# design.net
KiCad netlist of a schematic drawn in Altium Designer
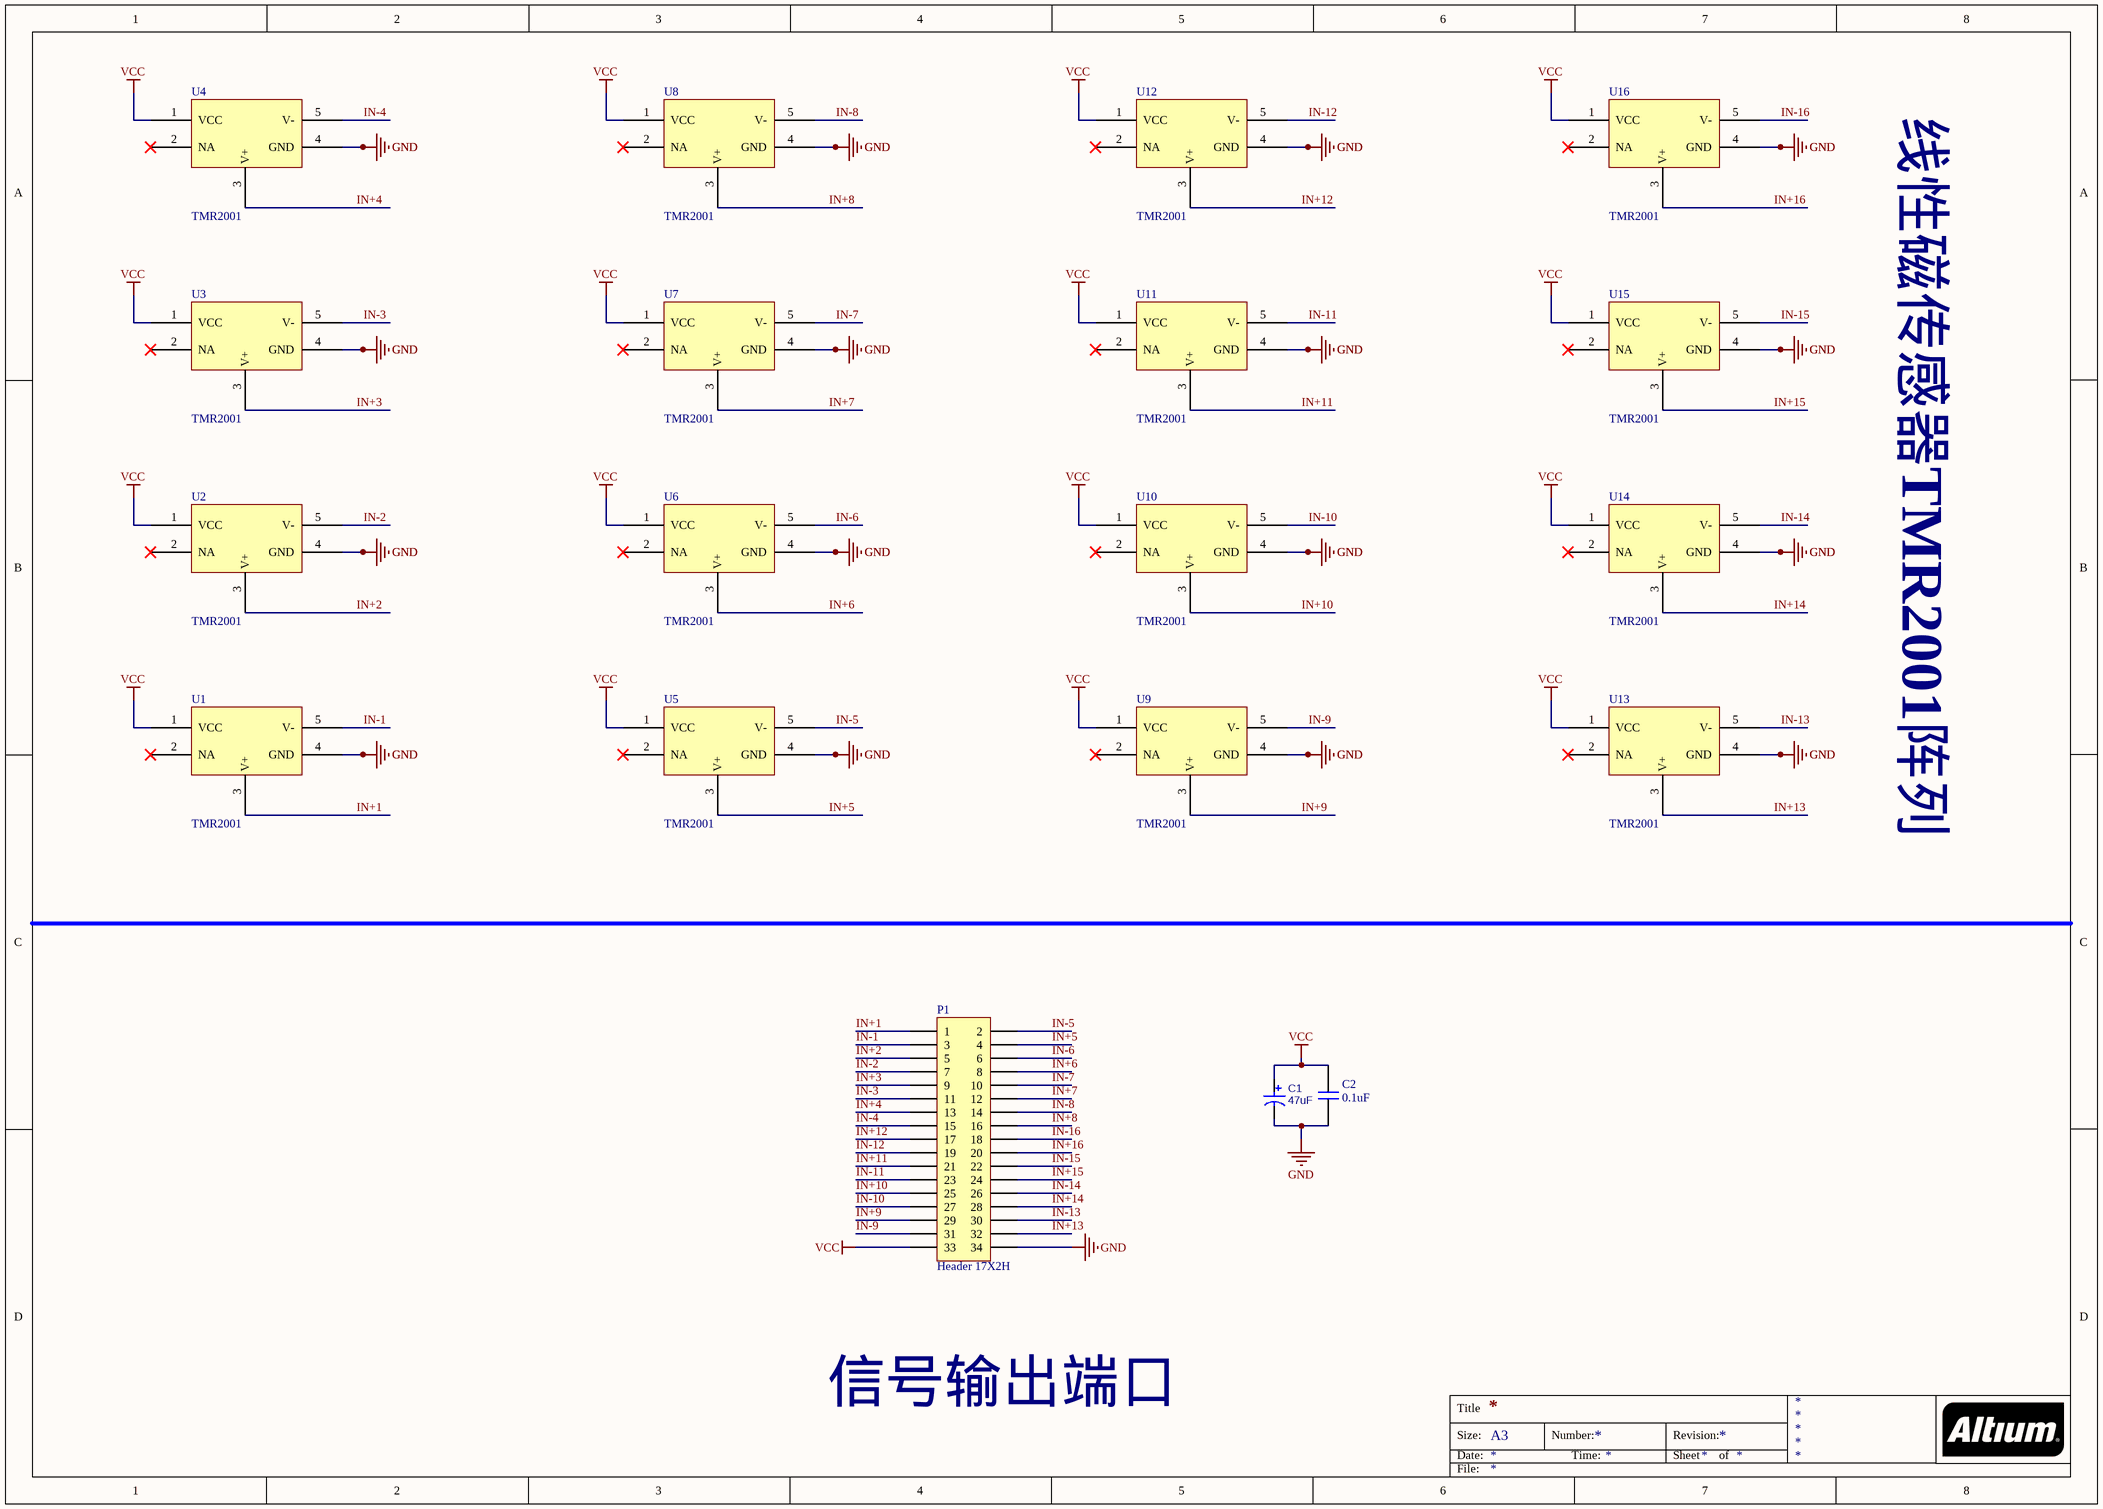
[diagram p0: 阵列磁传感器.SchDoc]

(export (version "E")
  (design (tool "Eeschema 10.0.6"))
  (components
    (comp (ref "C1")
      (value "47uF")
      (footprint "CAP-SMD_BD6.3-L6.6-W6.6-LS7.2-FD")
      (description "极性电解电容")
      (fields
        (field (name "BOM_MANUFACTURER PART") "Non - polar electrolytic capacitors10uf 100v")
        (field (name "BOM_SUPPLIER PART") "C56706")
      )
      (libsource (lib "毕业设计") (part "10uF"))
    )
    (comp (ref "C2")
      (value "0.1uF")
      (footprint "0805C")
      (description "普通电容")
      (libsource (lib "毕业设计") (part "CAP"))
    )
    (comp (ref "P1")
      (value "Header 17X2H")
      (footprint "HDR2X17")
      (description "Header, 17-Pin, Dual row, Right Angle")
      (fields (field (name "PUBLISHER") "Altium Limited"))
      (libsource (lib "Miscellaneous Connectors") (part "Header 17X2H"))
    )
    (comp (ref "U1")
      (value "TMR2001")
      (footprint "SOT95P280X145-5N")
      (description "线性磁传感器")
      (libsource (lib "毕业设计") (part "TMR2001"))
    )
    (comp (ref "U2")
      (value "TMR2001")
      (footprint "SOT95P280X145-5N")
      (description "线性磁传感器")
      (libsource (lib "毕业设计") (part "TMR2001"))
    )
    (comp (ref "U3")
      (value "TMR2001")
      (footprint "SOT95P280X145-5N")
      (description "线性磁传感器")
      (libsource (lib "毕业设计") (part "TMR2001"))
    )
    (comp (ref "U4")
      (value "TMR2001")
      (footprint "SOT95P280X145-5N")
      (description "线性磁传感器")
      (libsource (lib "毕业设计") (part "TMR2001"))
    )
    (comp (ref "U5")
      (value "TMR2001")
      (footprint "SOT95P280X145-5N")
      (description "线性磁传感器")
      (libsource (lib "毕业设计") (part "TMR2001"))
    )
    (comp (ref "U6")
      (value "TMR2001")
      (footprint "SOT95P280X145-5N")
      (description "线性磁传感器")
      (libsource (lib "毕业设计") (part "TMR2001"))
    )
    (comp (ref "U7")
      (value "TMR2001")
      (footprint "SOT95P280X145-5N")
      (description "线性磁传感器")
      (libsource (lib "毕业设计") (part "TMR2001"))
    )
    (comp (ref "U8")
      (value "TMR2001")
      (footprint "SOT95P280X145-5N")
      (description "线性磁传感器")
      (libsource (lib "毕业设计") (part "TMR2001"))
    )
    (comp (ref "U9")
      (value "TMR2001")
      (footprint "SOT95P280X145-5N")
      (description "线性磁传感器")
      (libsource (lib "毕业设计") (part "TMR2001"))
    )
    (comp (ref "U10")
      (value "TMR2001")
      (footprint "SOT95P280X145-5N")
      (description "线性磁传感器")
      (libsource (lib "毕业设计") (part "TMR2001"))
    )
    (comp (ref "U11")
      (value "TMR2001")
      (footprint "SOT95P280X145-5N")
      (description "线性磁传感器")
      (libsource (lib "毕业设计") (part "TMR2001"))
    )
    (comp (ref "U12")
      (value "TMR2001")
      (footprint "SOT95P280X145-5N")
      (description "线性磁传感器")
      (libsource (lib "毕业设计") (part "TMR2001"))
    )
    (comp (ref "U13")
      (value "TMR2001")
      (footprint "SOT95P280X145-5N")
      (description "线性磁传感器")
      (libsource (lib "毕业设计") (part "TMR2001"))
    )
    (comp (ref "U14")
      (value "TMR2001")
      (footprint "SOT95P280X145-5N")
      (description "线性磁传感器")
      (libsource (lib "毕业设计") (part "TMR2001"))
    )
    (comp (ref "U15")
      (value "TMR2001")
      (footprint "SOT95P280X145-5N")
      (description "线性磁传感器")
      (libsource (lib "毕业设计") (part "TMR2001"))
    )
    (comp (ref "U16")
      (value "TMR2001")
      (footprint "SOT95P280X145-5N")
      (description "线性磁传感器")
      (libsource (lib "毕业设计") (part "TMR2001"))
    )
  )
  (nets
    (net (code "1") (name "/IN+1") (class "Default")
      (node (ref "P1") (pin "1") (pinfunction "1_1") (pintype "passive"))
      (node (ref "U1") (pin "3") (pinfunction "V+_3") (pintype "passive"))
    )
    (net (code "2") (name "/IN+2") (class "Default")
      (node (ref "P1") (pin "5") (pinfunction "5_5") (pintype "passive"))
      (node (ref "U2") (pin "3") (pinfunction "V+_3") (pintype "passive"))
    )
    (net (code "3") (name "/IN+3") (class "Default")
      (node (ref "P1") (pin "9") (pinfunction "9_9") (pintype "passive"))
      (node (ref "U3") (pin "3") (pinfunction "V+_3") (pintype "passive"))
    )
    (net (code "4") (name "/IN+4") (class "Default")
      (node (ref "P1") (pin "13") (pinfunction "13_13") (pintype "passive"))
      (node (ref "U4") (pin "3") (pinfunction "V+_3") (pintype "passive"))
    )
    (net (code "5") (name "/IN+5") (class "Default")
      (node (ref "P1") (pin "4") (pinfunction "4_4") (pintype "passive"))
      (node (ref "U5") (pin "3") (pinfunction "V+_3") (pintype "passive"))
    )
    (net (code "6") (name "/IN+6") (class "Default")
      (node (ref "P1") (pin "8") (pinfunction "8_8") (pintype "passive"))
      (node (ref "U6") (pin "3") (pinfunction "V+_3") (pintype "passive"))
    )
    (net (code "7") (name "/IN+7") (class "Default")
      (node (ref "P1") (pin "12") (pinfunction "12_12") (pintype "passive"))
      (node (ref "U7") (pin "3") (pinfunction "V+_3") (pintype "passive"))
    )
    (net (code "8") (name "/IN+8") (class "Default")
      (node (ref "P1") (pin "16") (pinfunction "16_16") (pintype "passive"))
      (node (ref "U8") (pin "3") (pinfunction "V+_3") (pintype "passive"))
    )
    (net (code "9") (name "/IN+9") (class "Default")
      (node (ref "P1") (pin "29") (pinfunction "29_29") (pintype "passive"))
      (node (ref "U9") (pin "3") (pinfunction "V+_3") (pintype "passive"))
    )
    (net (code "10") (name "/IN+10") (class "Default")
      (node (ref "P1") (pin "25") (pinfunction "25_25") (pintype "passive"))
      (node (ref "U10") (pin "3") (pinfunction "V+_3") (pintype "passive"))
    )
    (net (code "11") (name "/IN+11") (class "Default")
      (node (ref "P1") (pin "21") (pinfunction "21_21") (pintype "passive"))
      (node (ref "U11") (pin "3") (pinfunction "V+_3") (pintype "passive"))
    )
    (net (code "12") (name "/IN+12") (class "Default")
      (node (ref "P1") (pin "17") (pinfunction "17_17") (pintype "passive"))
      (node (ref "U12") (pin "3") (pinfunction "V+_3") (pintype "passive"))
    )
    (net (code "13") (name "/IN+13") (class "Default")
      (node (ref "P1") (pin "32") (pinfunction "32_32") (pintype "passive"))
      (node (ref "U13") (pin "3") (pinfunction "V+_3") (pintype "passive"))
    )
    (net (code "14") (name "/IN+14") (class "Default")
      (node (ref "P1") (pin "28") (pinfunction "28_28") (pintype "passive"))
      (node (ref "U14") (pin "3") (pinfunction "V+_3") (pintype "passive"))
    )
    (net (code "15") (name "/IN+15") (class "Default")
      (node (ref "P1") (pin "24") (pinfunction "24_24") (pintype "passive"))
      (node (ref "U15") (pin "3") (pinfunction "V+_3") (pintype "passive"))
    )
    (net (code "16") (name "/IN+16") (class "Default")
      (node (ref "P1") (pin "20") (pinfunction "20_20") (pintype "passive"))
      (node (ref "U16") (pin "3") (pinfunction "V+_3") (pintype "passive"))
    )
    (net (code "17") (name "/IN-1") (class "Default")
      (node (ref "P1") (pin "3") (pinfunction "3_3") (pintype "passive"))
      (node (ref "U1") (pin "5") (pinfunction "V-_5") (pintype "passive"))
    )
    (net (code "18") (name "/IN-2") (class "Default")
      (node (ref "P1") (pin "7") (pinfunction "7_7") (pintype "passive"))
      (node (ref "U2") (pin "5") (pinfunction "V-_5") (pintype "passive"))
    )
    (net (code "19") (name "/IN-3") (class "Default")
      (node (ref "P1") (pin "11") (pinfunction "11_11") (pintype "passive"))
      (node (ref "U3") (pin "5") (pinfunction "V-_5") (pintype "passive"))
    )
    (net (code "20") (name "/IN-4") (class "Default")
      (node (ref "P1") (pin "15") (pinfunction "15_15") (pintype "passive"))
      (node (ref "U4") (pin "5") (pinfunction "V-_5") (pintype "passive"))
    )
    (net (code "21") (name "/IN-5") (class "Default")
      (node (ref "P1") (pin "2") (pinfunction "2_2") (pintype "passive"))
      (node (ref "U5") (pin "5") (pinfunction "V-_5") (pintype "passive"))
    )
    (net (code "22") (name "/IN-6") (class "Default")
      (node (ref "P1") (pin "6") (pinfunction "6_6") (pintype "passive"))
      (node (ref "U6") (pin "5") (pinfunction "V-_5") (pintype "passive"))
    )
    (net (code "23") (name "/IN-7") (class "Default")
      (node (ref "P1") (pin "10") (pinfunction "10_10") (pintype "passive"))
      (node (ref "U7") (pin "5") (pinfunction "V-_5") (pintype "passive"))
    )
    (net (code "24") (name "/IN-8") (class "Default")
      (node (ref "P1") (pin "14") (pinfunction "14_14") (pintype "passive"))
      (node (ref "U8") (pin "5") (pinfunction "V-_5") (pintype "passive"))
    )
    (net (code "25") (name "/IN-9") (class "Default")
      (node (ref "P1") (pin "31") (pinfunction "31_31") (pintype "passive"))
      (node (ref "U9") (pin "5") (pinfunction "V-_5") (pintype "passive"))
    )
    (net (code "26") (name "/IN-10") (class "Default")
      (node (ref "P1") (pin "27") (pinfunction "27_27") (pintype "passive"))
      (node (ref "U10") (pin "5") (pinfunction "V-_5") (pintype "passive"))
    )
    (net (code "27") (name "/IN-11") (class "Default")
      (node (ref "P1") (pin "23") (pinfunction "23_23") (pintype "passive"))
      (node (ref "U11") (pin "5") (pinfunction "V-_5") (pintype "passive"))
    )
    (net (code "28") (name "/IN-12") (class "Default")
      (node (ref "P1") (pin "19") (pinfunction "19_19") (pintype "passive"))
      (node (ref "U12") (pin "5") (pinfunction "V-_5") (pintype "passive"))
    )
    (net (code "29") (name "/IN-13") (class "Default")
      (node (ref "P1") (pin "30") (pinfunction "30_30") (pintype "passive"))
      (node (ref "U13") (pin "5") (pinfunction "V-_5") (pintype "passive"))
    )
    (net (code "30") (name "/IN-14") (class "Default")
      (node (ref "P1") (pin "26") (pinfunction "26_26") (pintype "passive"))
      (node (ref "U14") (pin "5") (pinfunction "V-_5") (pintype "passive"))
    )
    (net (code "31") (name "/IN-15") (class "Default")
      (node (ref "P1") (pin "22") (pinfunction "22_22") (pintype "passive"))
      (node (ref "U15") (pin "5") (pinfunction "V-_5") (pintype "passive"))
    )
    (net (code "32") (name "/IN-16") (class "Default")
      (node (ref "P1") (pin "18") (pinfunction "18_18") (pintype "passive"))
      (node (ref "U16") (pin "5") (pinfunction "V-_5") (pintype "passive"))
    )
    (net (code "33") (name "GND") (class "Default")
      (node (ref "C1") (pin "2") (pinfunction "2_2") (pintype "passive"))
      (node (ref "C2") (pin "1") (pinfunction "1_1") (pintype "passive"))
      (node (ref "P1") (pin "34") (pinfunction "34_34") (pintype "passive"))
      (node (ref "U1") (pin "4") (pinfunction "GND_4") (pintype "passive"))
      (node (ref "U10") (pin "4") (pinfunction "GND_4") (pintype "passive"))
      (node (ref "U11") (pin "4") (pinfunction "GND_4") (pintype "passive"))
      (node (ref "U12") (pin "4") (pinfunction "GND_4") (pintype "passive"))
      (node (ref "U13") (pin "4") (pinfunction "GND_4") (pintype "passive"))
      (node (ref "U14") (pin "4") (pinfunction "GND_4") (pintype "passive"))
      (node (ref "U15") (pin "4") (pinfunction "GND_4") (pintype "passive"))
      (node (ref "U16") (pin "4") (pinfunction "GND_4") (pintype "passive"))
      (node (ref "U2") (pin "4") (pinfunction "GND_4") (pintype "passive"))
      (node (ref "U3") (pin "4") (pinfunction "GND_4") (pintype "passive"))
      (node (ref "U4") (pin "4") (pinfunction "GND_4") (pintype "passive"))
      (node (ref "U5") (pin "4") (pinfunction "GND_4") (pintype "passive"))
      (node (ref "U6") (pin "4") (pinfunction "GND_4") (pintype "passive"))
      (node (ref "U7") (pin "4") (pinfunction "GND_4") (pintype "passive"))
      (node (ref "U8") (pin "4") (pinfunction "GND_4") (pintype "passive"))
      (node (ref "U9") (pin "4") (pinfunction "GND_4") (pintype "passive"))
    )
    (net (code "34") (name "VCC") (class "Default")
      (node (ref "C1") (pin "1") (pinfunction "1_1") (pintype "passive"))
      (node (ref "C2") (pin "2") (pinfunction "2_2") (pintype "passive"))
      (node (ref "P1") (pin "33") (pinfunction "33_33") (pintype "passive"))
      (node (ref "U1") (pin "1") (pinfunction "VCC_1") (pintype "passive"))
      (node (ref "U10") (pin "1") (pinfunction "VCC_1") (pintype "passive"))
      (node (ref "U11") (pin "1") (pinfunction "VCC_1") (pintype "passive"))
      (node (ref "U12") (pin "1") (pinfunction "VCC_1") (pintype "passive"))
      (node (ref "U13") (pin "1") (pinfunction "VCC_1") (pintype "passive"))
      (node (ref "U14") (pin "1") (pinfunction "VCC_1") (pintype "passive"))
      (node (ref "U15") (pin "1") (pinfunction "VCC_1") (pintype "passive"))
      (node (ref "U16") (pin "1") (pinfunction "VCC_1") (pintype "passive"))
      (node (ref "U2") (pin "1") (pinfunction "VCC_1") (pintype "passive"))
      (node (ref "U3") (pin "1") (pinfunction "VCC_1") (pintype "passive"))
      (node (ref "U4") (pin "1") (pinfunction "VCC_1") (pintype "passive"))
      (node (ref "U5") (pin "1") (pinfunction "VCC_1") (pintype "passive"))
      (node (ref "U6") (pin "1") (pinfunction "VCC_1") (pintype "passive"))
      (node (ref "U7") (pin "1") (pinfunction "VCC_1") (pintype "passive"))
      (node (ref "U8") (pin "1") (pinfunction "VCC_1") (pintype "passive"))
      (node (ref "U9") (pin "1") (pinfunction "VCC_1") (pintype "passive"))
    )
    (net (code "35") (name "unconnected-(U1-NA-Pad2)") (class "Default")
      (node (ref "U1") (pin "2") (pinfunction "NA_2") (pintype "passive+no_connect"))
    )
    (net (code "36") (name "unconnected-(U2-NA-Pad2)") (class "Default")
      (node (ref "U2") (pin "2") (pinfunction "NA_2") (pintype "passive+no_connect"))
    )
    (net (code "37") (name "unconnected-(U3-NA-Pad2)") (class "Default")
      (node (ref "U3") (pin "2") (pinfunction "NA_2") (pintype "passive+no_connect"))
    )
    (net (code "38") (name "unconnected-(U4-NA-Pad2)") (class "Default")
      (node (ref "U4") (pin "2") (pinfunction "NA_2") (pintype "passive+no_connect"))
    )
    (net (code "39") (name "unconnected-(U5-NA-Pad2)") (class "Default")
      (node (ref "U5") (pin "2") (pinfunction "NA_2") (pintype "passive+no_connect"))
    )
    (net (code "40") (name "unconnected-(U6-NA-Pad2)") (class "Default")
      (node (ref "U6") (pin "2") (pinfunction "NA_2") (pintype "passive+no_connect"))
    )
    (net (code "41") (name "unconnected-(U7-NA-Pad2)") (class "Default")
      (node (ref "U7") (pin "2") (pinfunction "NA_2") (pintype "passive+no_connect"))
    )
    (net (code "42") (name "unconnected-(U8-NA-Pad2)") (class "Default")
      (node (ref "U8") (pin "2") (pinfunction "NA_2") (pintype "passive+no_connect"))
    )
    (net (code "43") (name "unconnected-(U9-NA-Pad2)") (class "Default")
      (node (ref "U9") (pin "2") (pinfunction "NA_2") (pintype "passive+no_connect"))
    )
    (net (code "44") (name "unconnected-(U10-NA-Pad2)") (class "Default")
      (node (ref "U10") (pin "2") (pinfunction "NA_2") (pintype "passive+no_connect"))
    )
    (net (code "45") (name "unconnected-(U11-NA-Pad2)") (class "Default")
      (node (ref "U11") (pin "2") (pinfunction "NA_2") (pintype "passive+no_connect"))
    )
    (net (code "46") (name "unconnected-(U12-NA-Pad2)") (class "Default")
      (node (ref "U12") (pin "2") (pinfunction "NA_2") (pintype "passive+no_connect"))
    )
    (net (code "47") (name "unconnected-(U13-NA-Pad2)") (class "Default")
      (node (ref "U13") (pin "2") (pinfunction "NA_2") (pintype "passive+no_connect"))
    )
    (net (code "48") (name "unconnected-(U14-NA-Pad2)") (class "Default")
      (node (ref "U14") (pin "2") (pinfunction "NA_2") (pintype "passive+no_connect"))
    )
    (net (code "49") (name "unconnected-(U15-NA-Pad2)") (class "Default")
      (node (ref "U15") (pin "2") (pinfunction "NA_2") (pintype "passive+no_connect"))
    )
    (net (code "50") (name "unconnected-(U16-NA-Pad2)") (class "Default")
      (node (ref "U16") (pin "2") (pinfunction "NA_2") (pintype "passive+no_connect"))
    )
  )
)
